# lcd-gps-tracker.net
KiCad netlist of a schematic drawn in EAGLE
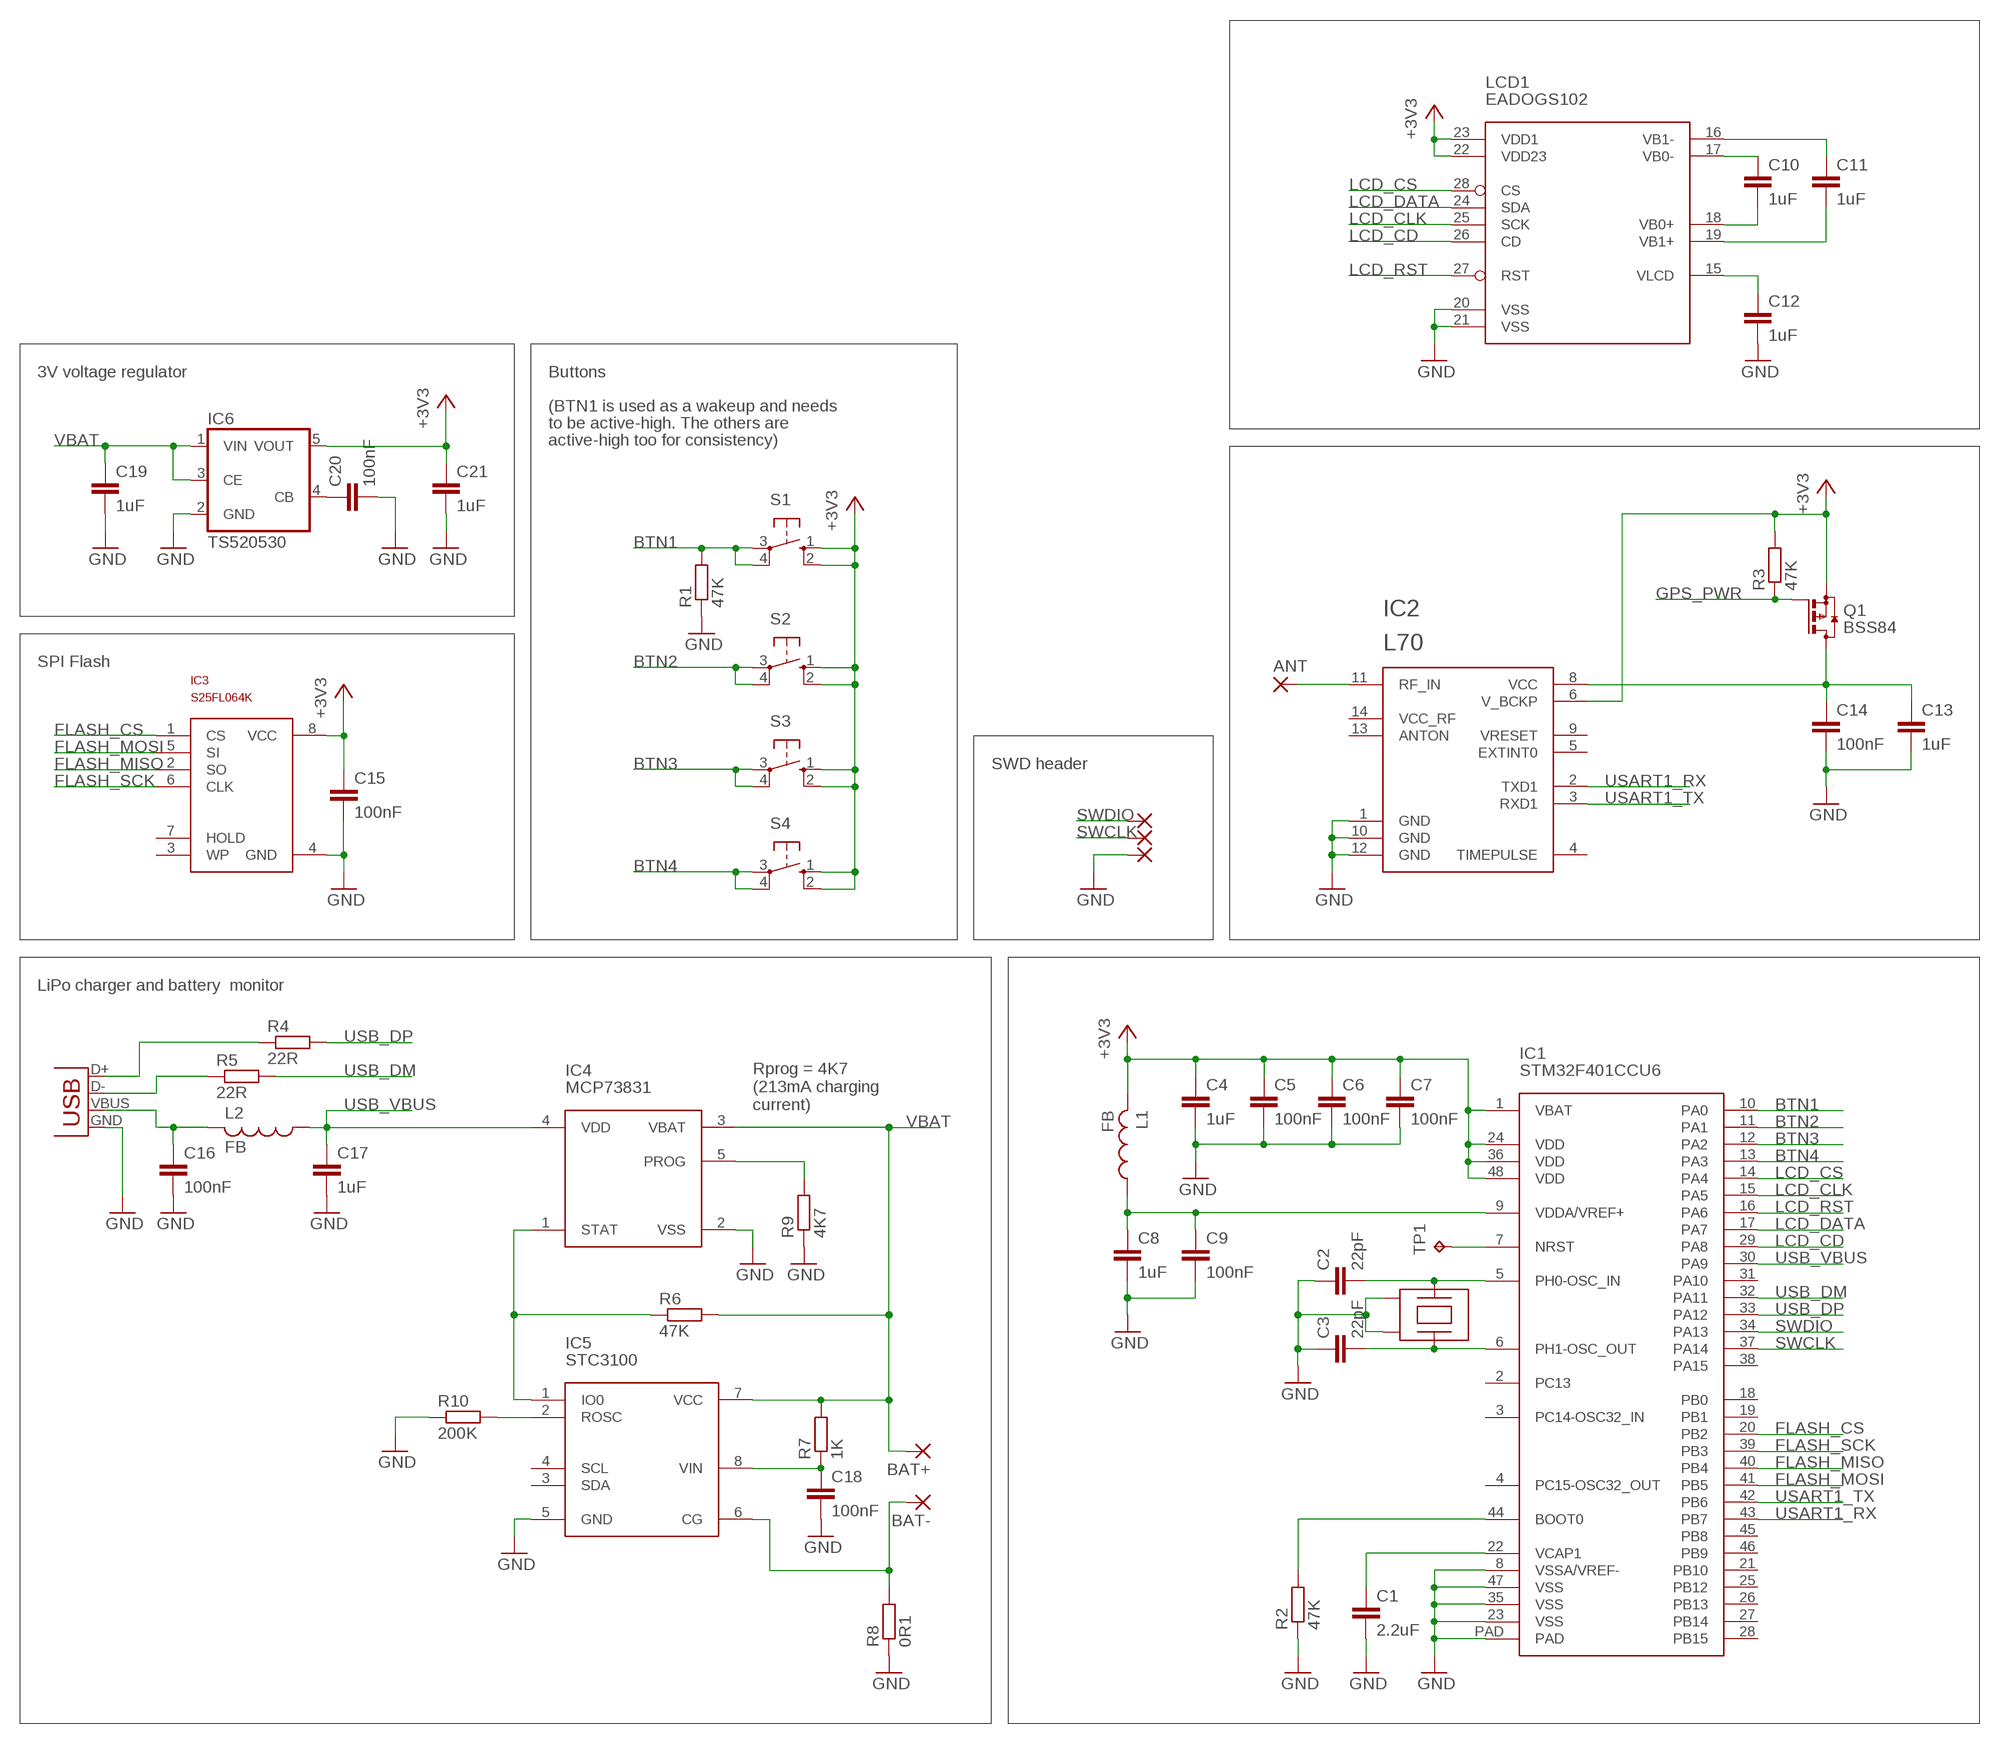
[diagram p0: schematic, sheet 1]

(export (version "E")
  (design (tool "Eeschema 10.0.6"))
  (components
    (comp (ref "ANT")
      (value "2,54/1,0")
      (footprint "eagle-import:2,54_1,0")
      (libsource (lib "eagle-import") (part "2,54/1,0"))
    )
    (comp (ref "BAT+")
      (value "SMD2")
      (footprint "eagle-import:SMD1,27-2,54")
      (libsource (lib "eagle-import") (part "SMD2"))
    )
    (comp (ref "BAT-")
      (value "SMD2")
      (footprint "eagle-import:SMD1,27-2,54")
      (libsource (lib "eagle-import") (part "SMD2"))
    )
    (comp (ref "C1")
      (value "2.2uF")
      (footprint "eagle-import:C0805")
      (libsource (lib "eagle-import") (part "C-EUC0805"))
    )
    (comp (ref "C2")
      (value "22pF")
      (footprint "eagle-import:C0603")
      (libsource (lib "eagle-import") (part "C-EUC0603"))
    )
    (comp (ref "C3")
      (value "22pF")
      (footprint "eagle-import:C0603")
      (libsource (lib "eagle-import") (part "C-EUC0603"))
    )
    (comp (ref "C4")
      (value "1uF")
      (footprint "eagle-import:C0603")
      (libsource (lib "eagle-import") (part "C-EUC0603"))
    )
    (comp (ref "C5")
      (value "100nF")
      (footprint "eagle-import:C0603")
      (libsource (lib "eagle-import") (part "C-EUC0603"))
    )
    (comp (ref "C6")
      (value "100nF")
      (footprint "eagle-import:C0603")
      (libsource (lib "eagle-import") (part "C-EUC0603"))
    )
    (comp (ref "C7")
      (value "100nF")
      (footprint "eagle-import:C0603")
      (libsource (lib "eagle-import") (part "C-EUC0603"))
    )
    (comp (ref "C8")
      (value "1uF")
      (footprint "eagle-import:C0603")
      (libsource (lib "eagle-import") (part "C-EUC0603"))
    )
    (comp (ref "C9")
      (value "100nF")
      (footprint "eagle-import:C0603")
      (libsource (lib "eagle-import") (part "C-EUC0603"))
    )
    (comp (ref "C10")
      (value "1uF")
      (footprint "eagle-import:C0603")
      (libsource (lib "eagle-import") (part "C-EUC0603"))
    )
    (comp (ref "C11")
      (value "1uF")
      (footprint "eagle-import:C0603")
      (libsource (lib "eagle-import") (part "C-EUC0603"))
    )
    (comp (ref "C12")
      (value "1uF")
      (footprint "eagle-import:C0603")
      (libsource (lib "eagle-import") (part "C-EUC0603"))
    )
    (comp (ref "C13")
      (value "1uF")
      (footprint "eagle-import:C0603")
      (libsource (lib "eagle-import") (part "C-EUC0603"))
    )
    (comp (ref "C14")
      (value "100nF")
      (footprint "eagle-import:C0603")
      (libsource (lib "eagle-import") (part "C-EUC0603"))
    )
    (comp (ref "C15")
      (value "100nF")
      (footprint "eagle-import:C0603")
      (libsource (lib "eagle-import") (part "C-EUC0603"))
    )
    (comp (ref "C16")
      (value "100nF")
      (footprint "eagle-import:C0603")
      (libsource (lib "eagle-import") (part "C-EUC0603"))
    )
    (comp (ref "C17")
      (value "1uF")
      (footprint "eagle-import:C0805")
      (libsource (lib "eagle-import") (part "C-EUC0805"))
    )
    (comp (ref "C18")
      (value "100nF")
      (footprint "eagle-import:C0603")
      (libsource (lib "eagle-import") (part "C-EUC0603"))
    )
    (comp (ref "C19")
      (value "1uF")
      (footprint "eagle-import:C0603")
      (libsource (lib "eagle-import") (part "C-EUC0603"))
    )
    (comp (ref "C20")
      (value "100nF")
      (footprint "eagle-import:C0603")
      (libsource (lib "eagle-import") (part "C-EUC0603"))
    )
    (comp (ref "C21")
      (value "1uF")
      (footprint "eagle-import:C0603")
      (libsource (lib "eagle-import") (part "C-EUC0603"))
    )
    (comp (ref "IC1")
      (value "STM32F401CCU6")
      (footprint "eagle-import:UFQFPN48")
      (libsource (lib "eagle-import") (part "STM32F401CCU6"))
    )
    (comp (ref "IC2")
      (value "L70")
      (footprint "eagle-import:L70")
      (libsource (lib "eagle-import") (part "L70"))
    )
    (comp (ref "IC3")
      (value "S25FL064K")
      (footprint "eagle-import:SO-08M")
      (libsource (lib "eagle-import") (part "S25FL064K"))
    )
    (comp (ref "IC4")
      (value "MCP73831")
      (footprint "eagle-import:SOT23-5")
      (libsource (lib "eagle-import") (part "MCP73831"))
    )
    (comp (ref "IC5")
      (value "STC3100")
      (footprint "eagle-import:MSOP8")
      (libsource (lib "eagle-import") (part "STC3100"))
    )
    (comp (ref "IC6")
      (value "TS520530")
      (footprint "eagle-import:SOT25")
      (libsource (lib "eagle-import") (part "TS520530"))
    )
    (comp (ref "L1")
      (value "FB")
      (footprint "eagle-import:L2012C")
      (libsource (lib "eagle-import") (part "L-USL2012C"))
    )
    (comp (ref "L2")
      (value "FB")
      (footprint "eagle-import:L2012C")
      (libsource (lib "eagle-import") (part "L-USL2012C"))
    )
    (comp (ref "LCD1")
      (value "EADOGS102")
      (footprint "eagle-import:EADOGS")
      (libsource (lib "eagle-import") (part "EADOGS102"))
    )
    (comp (ref "Q1")
      (value "BSS84")
      (footprint "eagle-import:SOT23")
      (libsource (lib "eagle-import") (part "BSS84"))
    )
    (comp (ref "R1")
      (value "47K")
      (footprint "eagle-import:R0603")
      (libsource (lib "eagle-import") (part "R-EU_R0603"))
    )
    (comp (ref "R2")
      (value "47K")
      (footprint "eagle-import:R0603")
      (libsource (lib "eagle-import") (part "R-EU_R0603"))
    )
    (comp (ref "R3")
      (value "47K")
      (footprint "eagle-import:R0603")
      (libsource (lib "eagle-import") (part "R-EU_R0603"))
    )
    (comp (ref "R4")
      (value "22R")
      (footprint "eagle-import:R0603")
      (libsource (lib "eagle-import") (part "R-EU_R0603"))
    )
    (comp (ref "R5")
      (value "22R")
      (footprint "eagle-import:R0603")
      (libsource (lib "eagle-import") (part "R-EU_R0603"))
    )
    (comp (ref "R6")
      (value "47K")
      (footprint "eagle-import:R0603")
      (libsource (lib "eagle-import") (part "R-EU_R0603"))
    )
    (comp (ref "R7")
      (value "1K")
      (footprint "eagle-import:R0603")
      (libsource (lib "eagle-import") (part "R-EU_R0603"))
    )
    (comp (ref "R8")
      (value "0R1")
      (footprint "eagle-import:R0805")
      (libsource (lib "eagle-import") (part "R-EU_R0805"))
    )
    (comp (ref "R9")
      (value "4K7")
      (footprint "eagle-import:R0603")
      (libsource (lib "eagle-import") (part "R-EU_R0603"))
    )
    (comp (ref "R10")
      (value "200K")
      (footprint "eagle-import:R0603")
      (libsource (lib "eagle-import") (part "R-EU_R0603"))
    )
    (comp (ref "S1")
      (value "10-XX")
      (footprint "eagle-import:B3F-10XX")
      (fields (field (name "MPN") "B3F-1000"))
      (libsource (lib "eagle-import") (part "10-XX"))
    )
    (comp (ref "S2")
      (value "10-XX")
      (footprint "eagle-import:B3F-10XX")
      (fields (field (name "MPN") "B3F-1000"))
      (libsource (lib "eagle-import") (part "10-XX"))
    )
    (comp (ref "S3")
      (value "10-XX")
      (footprint "eagle-import:B3F-10XX")
      (fields (field (name "MPN") "B3F-1000"))
      (libsource (lib "eagle-import") (part "10-XX"))
    )
    (comp (ref "S4")
      (value "10-XX")
      (footprint "eagle-import:B3F-10XX")
      (fields (field (name "MPN") "B3F-1000"))
      (libsource (lib "eagle-import") (part "10-XX"))
    )
    (comp (ref "SWCLK")
      (value "SMD2")
      (footprint "eagle-import:SMD1,27-2,54")
      (libsource (lib "eagle-import") (part "SMD2"))
    )
    (comp (ref "SWDIO")
      (value "SMD2")
      (footprint "eagle-import:SMD1,27-2,54")
      (libsource (lib "eagle-import") (part "SMD2"))
    )
    (comp (ref "SWGND")
      (value "SMD2")
      (footprint "eagle-import:SMD1,27-2,54")
      (libsource (lib "eagle-import") (part "SMD2"))
    )
    (comp (ref "TP1")
      (value "TPB1,27")
      (footprint "eagle-import:B1,27")
      (libsource (lib "eagle-import") (part "TPB1,27"))
    )
    (comp (ref "U$1")
      (value "XTAL-7M")
      (footprint "eagle-import:XTAL_7M")
      (libsource (lib "eagle-import") (part "XTAL-7M"))
    )
    (comp (ref "X1")
      (value "USB-MICROB")
      (footprint "eagle-import:USB-MICROB")
      (libsource (lib "eagle-import") (part "USB-MICROB"))
    )
  )
  (nets
    (net (code "1") (name "+3V3") (class "Default")
      (node (ref "C15") (pin "1") (pinfunction "1_1") (pintype "passive"))
      (node (ref "C21") (pin "1") (pinfunction "1_1") (pintype "passive"))
      (node (ref "C4") (pin "1") (pinfunction "1_1") (pintype "passive"))
      (node (ref "C5") (pin "1") (pinfunction "1_1") (pintype "passive"))
      (node (ref "C6") (pin "1") (pinfunction "1_1") (pintype "passive"))
      (node (ref "C7") (pin "1") (pinfunction "1_1") (pintype "passive"))
      (node (ref "IC1") (pin "1") (pinfunction "VBAT_1") (pintype "bidirectional"))
      (node (ref "IC1") (pin "24") (pinfunction "VDD_24") (pintype "bidirectional"))
      (node (ref "IC1") (pin "36") (pinfunction "VDD_36") (pintype "bidirectional"))
      (node (ref "IC1") (pin "48") (pinfunction "VDD_48") (pintype "bidirectional"))
      (node (ref "IC2") (pin "6") (pinfunction "V_BCKP_6") (pintype "bidirectional"))
      (node (ref "IC3") (pin "8") (pinfunction "VCC_8") (pintype "power_in"))
      (node (ref "IC6") (pin "5") (pinfunction "VOUT_5") (pintype "passive"))
      (node (ref "L1") (pin "2") (pinfunction "2_2") (pintype "passive"))
      (node (ref "LCD1") (pin "22") (pinfunction "VDD23_22") (pintype "bidirectional"))
      (node (ref "LCD1") (pin "23") (pinfunction "VDD1_23") (pintype "bidirectional"))
      (node (ref "Q1") (pin "2") (pinfunction "S_2") (pintype "passive"))
      (node (ref "R3") (pin "2") (pinfunction "2_2") (pintype "passive"))
      (node (ref "S1") (pin "1") (pinfunction "S_1") (pintype "passive"))
      (node (ref "S1") (pin "2") (pinfunction "S1_2") (pintype "passive"))
      (node (ref "S2") (pin "1") (pinfunction "S_1") (pintype "passive"))
      (node (ref "S2") (pin "2") (pinfunction "S1_2") (pintype "passive"))
      (node (ref "S3") (pin "1") (pinfunction "S_1") (pintype "passive"))
      (node (ref "S3") (pin "2") (pinfunction "S1_2") (pintype "passive"))
      (node (ref "S4") (pin "1") (pinfunction "S_1") (pintype "passive"))
      (node (ref "S4") (pin "2") (pinfunction "S1_2") (pintype "passive"))
    )
    (net (code "2") (name "/BTN1") (class "Default")
      (node (ref "IC1") (pin "10") (pinfunction "PA0_10") (pintype "bidirectional"))
      (node (ref "R1") (pin "2") (pinfunction "2_2") (pintype "passive"))
      (node (ref "S1") (pin "3") (pinfunction "P_3") (pintype "passive"))
      (node (ref "S1") (pin "4") (pinfunction "P1_4") (pintype "passive"))
    )
    (net (code "3") (name "/BTN2") (class "Default")
      (node (ref "IC1") (pin "11") (pinfunction "PA1_11") (pintype "bidirectional"))
      (node (ref "S2") (pin "3") (pinfunction "P_3") (pintype "passive"))
      (node (ref "S2") (pin "4") (pinfunction "P1_4") (pintype "passive"))
    )
    (net (code "4") (name "/BTN3") (class "Default")
      (node (ref "IC1") (pin "12") (pinfunction "PA2_12") (pintype "bidirectional"))
      (node (ref "S3") (pin "3") (pinfunction "P_3") (pintype "passive"))
      (node (ref "S3") (pin "4") (pinfunction "P1_4") (pintype "passive"))
    )
    (net (code "5") (name "/BTN4") (class "Default")
      (node (ref "IC1") (pin "13") (pinfunction "PA3_13") (pintype "bidirectional"))
      (node (ref "S4") (pin "3") (pinfunction "P_3") (pintype "passive"))
      (node (ref "S4") (pin "4") (pinfunction "P1_4") (pintype "passive"))
    )
    (net (code "6") (name "/FLASH_CS") (class "Default")
      (node (ref "IC1") (pin "20") (pinfunction "PB2_20") (pintype "bidirectional"))
      (node (ref "IC3") (pin "1") (pinfunction "CS_1") (pintype "bidirectional"))
    )
    (net (code "7") (name "/FLASH_MISO") (class "Default")
      (node (ref "IC1") (pin "40") (pinfunction "PB4_40") (pintype "bidirectional"))
      (node (ref "IC3") (pin "2") (pinfunction "SO_2") (pintype "bidirectional"))
    )
    (net (code "8") (name "/FLASH_MOSI") (class "Default")
      (node (ref "IC1") (pin "41") (pinfunction "PB5_41") (pintype "bidirectional"))
      (node (ref "IC3") (pin "5") (pinfunction "SI_5") (pintype "bidirectional"))
    )
    (net (code "9") (name "/FLASH_SCK") (class "Default")
      (node (ref "IC1") (pin "39") (pinfunction "PB3_39") (pintype "bidirectional"))
      (node (ref "IC3") (pin "6") (pinfunction "CLK_6") (pintype "bidirectional"))
    )
    (net (code "10") (name "/GPS_PWR") (class "Default")
      (node (ref "Q1") (pin "1") (pinfunction "G_1") (pintype "passive"))
      (node (ref "R3") (pin "1") (pinfunction "1_1") (pintype "passive"))
    )
    (net (code "11") (name "/LCD_CD") (class "Default")
      (node (ref "IC1") (pin "29") (pinfunction "PA8_29") (pintype "bidirectional"))
      (node (ref "LCD1") (pin "26") (pinfunction "CD_26") (pintype "bidirectional"))
    )
    (net (code "12") (name "/LCD_CLK") (class "Default")
      (node (ref "IC1") (pin "15") (pinfunction "PA5_15") (pintype "bidirectional"))
      (node (ref "LCD1") (pin "25") (pinfunction "SCK_25") (pintype "bidirectional"))
    )
    (net (code "13") (name "/LCD_CS") (class "Default")
      (node (ref "IC1") (pin "14") (pinfunction "PA4_14") (pintype "bidirectional"))
      (node (ref "LCD1") (pin "28") (pinfunction "CS_28") (pintype "bidirectional"))
    )
    (net (code "14") (name "/LCD_DATA") (class "Default")
      (node (ref "IC1") (pin "17") (pinfunction "PA7_17") (pintype "bidirectional"))
      (node (ref "LCD1") (pin "24") (pinfunction "SDA_24") (pintype "bidirectional"))
    )
    (net (code "15") (name "/LCD_RST") (class "Default")
      (node (ref "IC1") (pin "16") (pinfunction "PA6_16") (pintype "bidirectional"))
      (node (ref "LCD1") (pin "27") (pinfunction "RST_27") (pintype "bidirectional"))
    )
    (net (code "16") (name "/SWCLK") (class "Default")
      (node (ref "IC1") (pin "37") (pinfunction "PA14_37") (pintype "bidirectional"))
      (node (ref "SWCLK") (pin "1") (pinfunction "P_1") (pintype "passive"))
    )
    (net (code "17") (name "/SWDIO") (class "Default")
      (node (ref "IC1") (pin "34") (pinfunction "PA13_34") (pintype "bidirectional"))
      (node (ref "SWDIO") (pin "1") (pinfunction "P_1") (pintype "passive"))
    )
    (net (code "18") (name "/USART1_RX") (class "Default")
      (node (ref "IC1") (pin "43") (pinfunction "PB7_43") (pintype "bidirectional"))
      (node (ref "IC2") (pin "2") (pinfunction "TXD1_2") (pintype "bidirectional"))
    )
    (net (code "19") (name "/USART1_TX") (class "Default")
      (node (ref "IC1") (pin "42") (pinfunction "PB6_42") (pintype "bidirectional"))
      (node (ref "IC2") (pin "3") (pinfunction "RXD1_3") (pintype "bidirectional"))
    )
    (net (code "20") (name "/USB_DM") (class "Default")
      (node (ref "IC1") (pin "32") (pinfunction "PA11_32") (pintype "bidirectional"))
      (node (ref "R5") (pin "2") (pinfunction "2_2") (pintype "passive"))
    )
    (net (code "21") (name "/USB_DP") (class "Default")
      (node (ref "IC1") (pin "33") (pinfunction "PA12_33") (pintype "bidirectional"))
      (node (ref "R4") (pin "2") (pinfunction "2_2") (pintype "passive"))
    )
    (net (code "22") (name "/USB_VBUS") (class "Default")
      (node (ref "C17") (pin "1") (pinfunction "1_1") (pintype "passive"))
      (node (ref "IC1") (pin "30") (pinfunction "PA9_30") (pintype "bidirectional"))
      (node (ref "IC4") (pin "4") (pinfunction "VDD_4") (pintype "bidirectional"))
      (node (ref "L2") (pin "1") (pinfunction "1_1") (pintype "passive"))
    )
    (net (code "23") (name "/VBAT") (class "Default")
      (node (ref "BAT+") (pin "1") (pinfunction "P_1") (pintype "passive"))
      (node (ref "C19") (pin "1") (pinfunction "1_1") (pintype "passive"))
      (node (ref "IC4") (pin "3") (pinfunction "VBAT_3") (pintype "bidirectional"))
      (node (ref "IC5") (pin "7") (pinfunction "VCC_7") (pintype "power_in"))
      (node (ref "IC6") (pin "1") (pinfunction "VIN_1") (pintype "input"))
      (node (ref "IC6") (pin "3") (pinfunction "CE_3") (pintype "input"))
      (node (ref "R6") (pin "2") (pinfunction "2_2") (pintype "passive"))
      (node (ref "R7") (pin "2") (pinfunction "2_2") (pintype "passive"))
    )
    (net (code "24") (name "GND") (class "Default")
      (node (ref "C1") (pin "2") (pinfunction "2_2") (pintype "passive"))
      (node (ref "C12") (pin "2") (pinfunction "2_2") (pintype "passive"))
      (node (ref "C13") (pin "2") (pinfunction "2_2") (pintype "passive"))
      (node (ref "C14") (pin "2") (pinfunction "2_2") (pintype "passive"))
      (node (ref "C15") (pin "2") (pinfunction "2_2") (pintype "passive"))
      (node (ref "C16") (pin "2") (pinfunction "2_2") (pintype "passive"))
      (node (ref "C17") (pin "2") (pinfunction "2_2") (pintype "passive"))
      (node (ref "C18") (pin "2") (pinfunction "2_2") (pintype "passive"))
      (node (ref "C19") (pin "2") (pinfunction "2_2") (pintype "passive"))
      (node (ref "C2") (pin "1") (pinfunction "1_1") (pintype "passive"))
      (node (ref "C20") (pin "2") (pinfunction "2_2") (pintype "passive"))
      (node (ref "C21") (pin "2") (pinfunction "2_2") (pintype "passive"))
      (node (ref "C3") (pin "1") (pinfunction "1_1") (pintype "passive"))
      (node (ref "C4") (pin "2") (pinfunction "2_2") (pintype "passive"))
      (node (ref "C5") (pin "2") (pinfunction "2_2") (pintype "passive"))
      (node (ref "C6") (pin "2") (pinfunction "2_2") (pintype "passive"))
      (node (ref "C7") (pin "2") (pinfunction "2_2") (pintype "passive"))
      (node (ref "C8") (pin "2") (pinfunction "2_2") (pintype "passive"))
      (node (ref "C9") (pin "2") (pinfunction "2_2") (pintype "passive"))
      (node (ref "IC1") (pin "23") (pinfunction "VSS_23") (pintype "bidirectional"))
      (node (ref "IC1") (pin "35") (pinfunction "VSS_35") (pintype "bidirectional"))
      (node (ref "IC1") (pin "47") (pinfunction "VSS_47") (pintype "bidirectional"))
      (node (ref "IC1") (pin "8") (pinfunction "VSSA/VREF-_8") (pintype "bidirectional"))
      (node (ref "IC1") (pin "PAD") (pinfunction "PAD_PAD") (pintype "bidirectional"))
      (node (ref "IC2") (pin "1") (pinfunction "GND_1") (pintype "bidirectional"))
      (node (ref "IC2") (pin "10") (pinfunction "GND_10") (pintype "bidirectional"))
      (node (ref "IC2") (pin "12") (pinfunction "GND_12") (pintype "bidirectional"))
      (node (ref "IC3") (pin "4") (pinfunction "GND_4") (pintype "power_in"))
      (node (ref "IC4") (pin "2") (pinfunction "VSS_2") (pintype "bidirectional"))
      (node (ref "IC5") (pin "5") (pinfunction "GND_5") (pintype "power_in"))
      (node (ref "IC6") (pin "2") (pinfunction "GND_2") (pintype "passive"))
      (node (ref "LCD1") (pin "20") (pinfunction "VSS_20") (pintype "bidirectional"))
      (node (ref "LCD1") (pin "21") (pinfunction "VSS_21") (pintype "bidirectional"))
      (node (ref "R1") (pin "1") (pinfunction "1_1") (pintype "passive"))
      (node (ref "R10") (pin "1") (pinfunction "1_1") (pintype "passive"))
      (node (ref "R2") (pin "1") (pinfunction "1_1") (pintype "passive"))
      (node (ref "R8") (pin "1") (pinfunction "1_1") (pintype "passive"))
      (node (ref "R9") (pin "1") (pinfunction "1_1") (pintype "passive"))
      (node (ref "SWGND") (pin "1") (pinfunction "P_1") (pintype "passive"))
      (node (ref "U$1") (pin "2") (pinfunction "G1_2") (pintype "bidirectional"))
      (node (ref "U$1") (pin "4") (pinfunction "G2_4") (pintype "bidirectional"))
      (node (ref "X1") (pin "GND") (pinfunction "GND_GND") (pintype "bidirectional"))
    )
    (net (code "25") (name "Net-(ANT-P)") (class "Default")
      (node (ref "ANT") (pin "1") (pinfunction "P_1") (pintype "passive"))
      (node (ref "IC2") (pin "11") (pinfunction "RF_IN_11") (pintype "bidirectional"))
    )
    (net (code "26") (name "Net-(BAT--P)") (class "Default")
      (node (ref "BAT-") (pin "1") (pinfunction "P_1") (pintype "passive"))
      (node (ref "IC5") (pin "6") (pinfunction "CG_6") (pintype "input"))
      (node (ref "R8") (pin "2") (pinfunction "2_2") (pintype "passive"))
    )
    (net (code "27") (name "Net-(C16-Pad1)") (class "Default")
      (node (ref "C16") (pin "1") (pinfunction "1_1") (pintype "passive"))
      (node (ref "L2") (pin "2") (pinfunction "2_2") (pintype "passive"))
      (node (ref "X1") (pin "VBUS") (pinfunction "VBUS_VBUS") (pintype "bidirectional"))
    )
    (net (code "28") (name "Net-(IC1-BOOT0)") (class "Default")
      (node (ref "IC1") (pin "44") (pinfunction "BOOT0_44") (pintype "bidirectional"))
      (node (ref "R2") (pin "2") (pinfunction "2_2") (pintype "passive"))
    )
    (net (code "29") (name "Net-(IC1-NRST)") (class "Default")
      (node (ref "IC1") (pin "7") (pinfunction "NRST_7") (pintype "bidirectional"))
      (node (ref "TP1") (pin "TP") (pinfunction "TP_TP") (pintype "input"))
    )
    (net (code "30") (name "Net-(IC1-PH0-OSC_IN)") (class "Default")
      (node (ref "C2") (pin "2") (pinfunction "2_2") (pintype "passive"))
      (node (ref "IC1") (pin "5") (pinfunction "PH0-OSC_IN_5") (pintype "bidirectional"))
      (node (ref "U$1") (pin "1") (pinfunction "1_1") (pintype "bidirectional"))
    )
    (net (code "31") (name "Net-(IC1-PH1-OSC_OUT)") (class "Default")
      (node (ref "C3") (pin "2") (pinfunction "2_2") (pintype "passive"))
      (node (ref "IC1") (pin "6") (pinfunction "PH1-OSC_OUT_6") (pintype "bidirectional"))
      (node (ref "U$1") (pin "3") (pinfunction "2_3") (pintype "bidirectional"))
    )
    (net (code "32") (name "Net-(IC1-VCAP1)") (class "Default")
      (node (ref "C1") (pin "1") (pinfunction "1_1") (pintype "passive"))
      (node (ref "IC1") (pin "22") (pinfunction "VCAP1_22") (pintype "bidirectional"))
    )
    (net (code "33") (name "Net-(IC1-VDDA{slash}VREF+)") (class "Default")
      (node (ref "C8") (pin "1") (pinfunction "1_1") (pintype "passive"))
      (node (ref "C9") (pin "1") (pinfunction "1_1") (pintype "passive"))
      (node (ref "IC1") (pin "9") (pinfunction "VDDA/VREF+_9") (pintype "bidirectional"))
      (node (ref "L1") (pin "1") (pinfunction "1_1") (pintype "passive"))
    )
    (net (code "34") (name "Net-(IC2-VCC)") (class "Default")
      (node (ref "C13") (pin "1") (pinfunction "1_1") (pintype "passive"))
      (node (ref "C14") (pin "1") (pinfunction "1_1") (pintype "passive"))
      (node (ref "IC2") (pin "8") (pinfunction "VCC_8") (pintype "bidirectional"))
      (node (ref "Q1") (pin "3") (pinfunction "D_3") (pintype "passive"))
    )
    (net (code "35") (name "Net-(IC4-PROG)") (class "Default")
      (node (ref "IC4") (pin "5") (pinfunction "PROG_5") (pintype "bidirectional"))
      (node (ref "R9") (pin "2") (pinfunction "2_2") (pintype "passive"))
    )
    (net (code "36") (name "Net-(IC4-STAT)") (class "Default")
      (node (ref "IC4") (pin "1") (pinfunction "STAT_1") (pintype "bidirectional"))
      (node (ref "IC5") (pin "1") (pinfunction "IO0_1") (pintype "bidirectional"))
      (node (ref "R6") (pin "1") (pinfunction "1_1") (pintype "passive"))
    )
    (net (code "37") (name "Net-(IC5-ROSC)") (class "Default")
      (node (ref "IC5") (pin "2") (pinfunction "ROSC_2") (pintype "bidirectional"))
      (node (ref "R10") (pin "2") (pinfunction "2_2") (pintype "passive"))
    )
    (net (code "38") (name "Net-(IC5-VIN)") (class "Default")
      (node (ref "C18") (pin "1") (pinfunction "1_1") (pintype "passive"))
      (node (ref "IC5") (pin "8") (pinfunction "VIN_8") (pintype "input"))
      (node (ref "R7") (pin "1") (pinfunction "1_1") (pintype "passive"))
    )
    (net (code "39") (name "Net-(IC6-CB)") (class "Default")
      (node (ref "C20") (pin "1") (pinfunction "1_1") (pintype "passive"))
      (node (ref "IC6") (pin "4") (pinfunction "CB_4") (pintype "input"))
    )
    (net (code "40") (name "Net-(LCD1-VB0+)") (class "Default")
      (node (ref "C10") (pin "2") (pinfunction "2_2") (pintype "passive"))
      (node (ref "LCD1") (pin "18") (pinfunction "VB0+_18") (pintype "bidirectional"))
    )
    (net (code "41") (name "Net-(LCD1-VB0-)") (class "Default")
      (node (ref "C10") (pin "1") (pinfunction "1_1") (pintype "passive"))
      (node (ref "LCD1") (pin "17") (pinfunction "VB0-_17") (pintype "bidirectional"))
    )
    (net (code "42") (name "Net-(LCD1-VB1+)") (class "Default")
      (node (ref "C11") (pin "2") (pinfunction "2_2") (pintype "passive"))
      (node (ref "LCD1") (pin "19") (pinfunction "VB1+_19") (pintype "bidirectional"))
    )
    (net (code "43") (name "Net-(LCD1-VB1-)") (class "Default")
      (node (ref "C11") (pin "1") (pinfunction "1_1") (pintype "passive"))
      (node (ref "LCD1") (pin "16") (pinfunction "VB1-_16") (pintype "bidirectional"))
    )
    (net (code "44") (name "Net-(LCD1-VLCD)") (class "Default")
      (node (ref "C12") (pin "1") (pinfunction "1_1") (pintype "passive"))
      (node (ref "LCD1") (pin "15") (pinfunction "VLCD_15") (pintype "bidirectional"))
    )
    (net (code "45") (name "Net-(R4-Pad1)") (class "Default")
      (node (ref "R4") (pin "1") (pinfunction "1_1") (pintype "passive"))
      (node (ref "X1") (pin "D+") (pinfunction "D+_D+") (pintype "bidirectional"))
    )
    (net (code "46") (name "Net-(R5-Pad1)") (class "Default")
      (node (ref "R5") (pin "1") (pinfunction "1_1") (pintype "passive"))
      (node (ref "X1") (pin "D-") (pinfunction "D-_D-") (pintype "bidirectional"))
    )
    (net (code "47") (name "unconnected-(IC1-PA10-Pad31)") (class "Default")
      (node (ref "IC1") (pin "31") (pinfunction "PA10_31") (pintype "bidirectional"))
    )
    (net (code "48") (name "unconnected-(IC1-PA15-Pad38)") (class "Default")
      (node (ref "IC1") (pin "38") (pinfunction "PA15_38") (pintype "bidirectional"))
    )
    (net (code "49") (name "unconnected-(IC1-PB0-Pad18)") (class "Default")
      (node (ref "IC1") (pin "18") (pinfunction "PB0_18") (pintype "bidirectional"))
    )
    (net (code "50") (name "unconnected-(IC1-PB1-Pad19)") (class "Default")
      (node (ref "IC1") (pin "19") (pinfunction "PB1_19") (pintype "bidirectional"))
    )
    (net (code "51") (name "unconnected-(IC1-PB8-Pad45)") (class "Default")
      (node (ref "IC1") (pin "45") (pinfunction "PB8_45") (pintype "bidirectional"))
    )
    (net (code "52") (name "unconnected-(IC1-PB9-Pad46)") (class "Default")
      (node (ref "IC1") (pin "46") (pinfunction "PB9_46") (pintype "bidirectional"))
    )
    (net (code "53") (name "unconnected-(IC1-PB10-Pad21)") (class "Default")
      (node (ref "IC1") (pin "21") (pinfunction "PB10_21") (pintype "bidirectional"))
    )
    (net (code "54") (name "unconnected-(IC1-PB12-Pad25)") (class "Default")
      (node (ref "IC1") (pin "25") (pinfunction "PB12_25") (pintype "bidirectional"))
    )
    (net (code "55") (name "unconnected-(IC1-PB13-Pad26)") (class "Default")
      (node (ref "IC1") (pin "26") (pinfunction "PB13_26") (pintype "bidirectional"))
    )
    (net (code "56") (name "unconnected-(IC1-PB14-Pad27)") (class "Default")
      (node (ref "IC1") (pin "27") (pinfunction "PB14_27") (pintype "bidirectional"))
    )
    (net (code "57") (name "unconnected-(IC1-PB15-Pad28)") (class "Default")
      (node (ref "IC1") (pin "28") (pinfunction "PB15_28") (pintype "bidirectional"))
    )
    (net (code "58") (name "unconnected-(IC1-PC13-Pad2)") (class "Default")
      (node (ref "IC1") (pin "2") (pinfunction "PC13_2") (pintype "bidirectional"))
    )
    (net (code "59") (name "unconnected-(IC1-PC14-OSC32_IN-Pad3)") (class "Default")
      (node (ref "IC1") (pin "3") (pinfunction "PC14-OSC32_IN_3") (pintype "bidirectional"))
    )
    (net (code "60") (name "unconnected-(IC1-PC15-OSC32_OUT-Pad4)") (class "Default")
      (node (ref "IC1") (pin "4") (pinfunction "PC15-OSC32_OUT_4") (pintype "bidirectional"))
    )
    (net (code "61") (name "unconnected-(IC2-ANTON-Pad13)") (class "Default")
      (node (ref "IC2") (pin "13") (pinfunction "ANTON_13") (pintype "bidirectional"))
    )
    (net (code "62") (name "unconnected-(IC2-EXTINT0-Pad5)") (class "Default")
      (node (ref "IC2") (pin "5") (pinfunction "EXTINT0_5") (pintype "bidirectional"))
    )
    (net (code "63") (name "unconnected-(IC2-TIMEPULSE-Pad4)") (class "Default")
      (node (ref "IC2") (pin "4") (pinfunction "TIMEPULSE_4") (pintype "bidirectional"))
    )
    (net (code "64") (name "unconnected-(IC2-VCC_RF-Pad14)") (class "Default")
      (node (ref "IC2") (pin "14") (pinfunction "VCC_RF_14") (pintype "bidirectional"))
    )
    (net (code "65") (name "unconnected-(IC2-VRESET-Pad9)") (class "Default")
      (node (ref "IC2") (pin "9") (pinfunction "VRESET_9") (pintype "bidirectional"))
    )
    (net (code "66") (name "unconnected-(IC3-HOLD-Pad7)") (class "Default")
      (node (ref "IC3") (pin "7") (pinfunction "HOLD_7") (pintype "bidirectional"))
    )
    (net (code "67") (name "unconnected-(IC3-WP-Pad3)") (class "Default")
      (node (ref "IC3") (pin "3") (pinfunction "WP_3") (pintype "bidirectional"))
    )
    (net (code "68") (name "unconnected-(IC5-SCL-Pad4)") (class "Default")
      (node (ref "IC5") (pin "4") (pinfunction "SCL_4") (pintype "bidirectional"))
    )
    (net (code "69") (name "unconnected-(IC5-SDA-Pad3)") (class "Default")
      (node (ref "IC5") (pin "3") (pinfunction "SDA_3") (pintype "bidirectional"))
    )
  )
)
